# eurorack-passive-logic-or.net
KiCad netlist of a schematic drawn in EAGLE
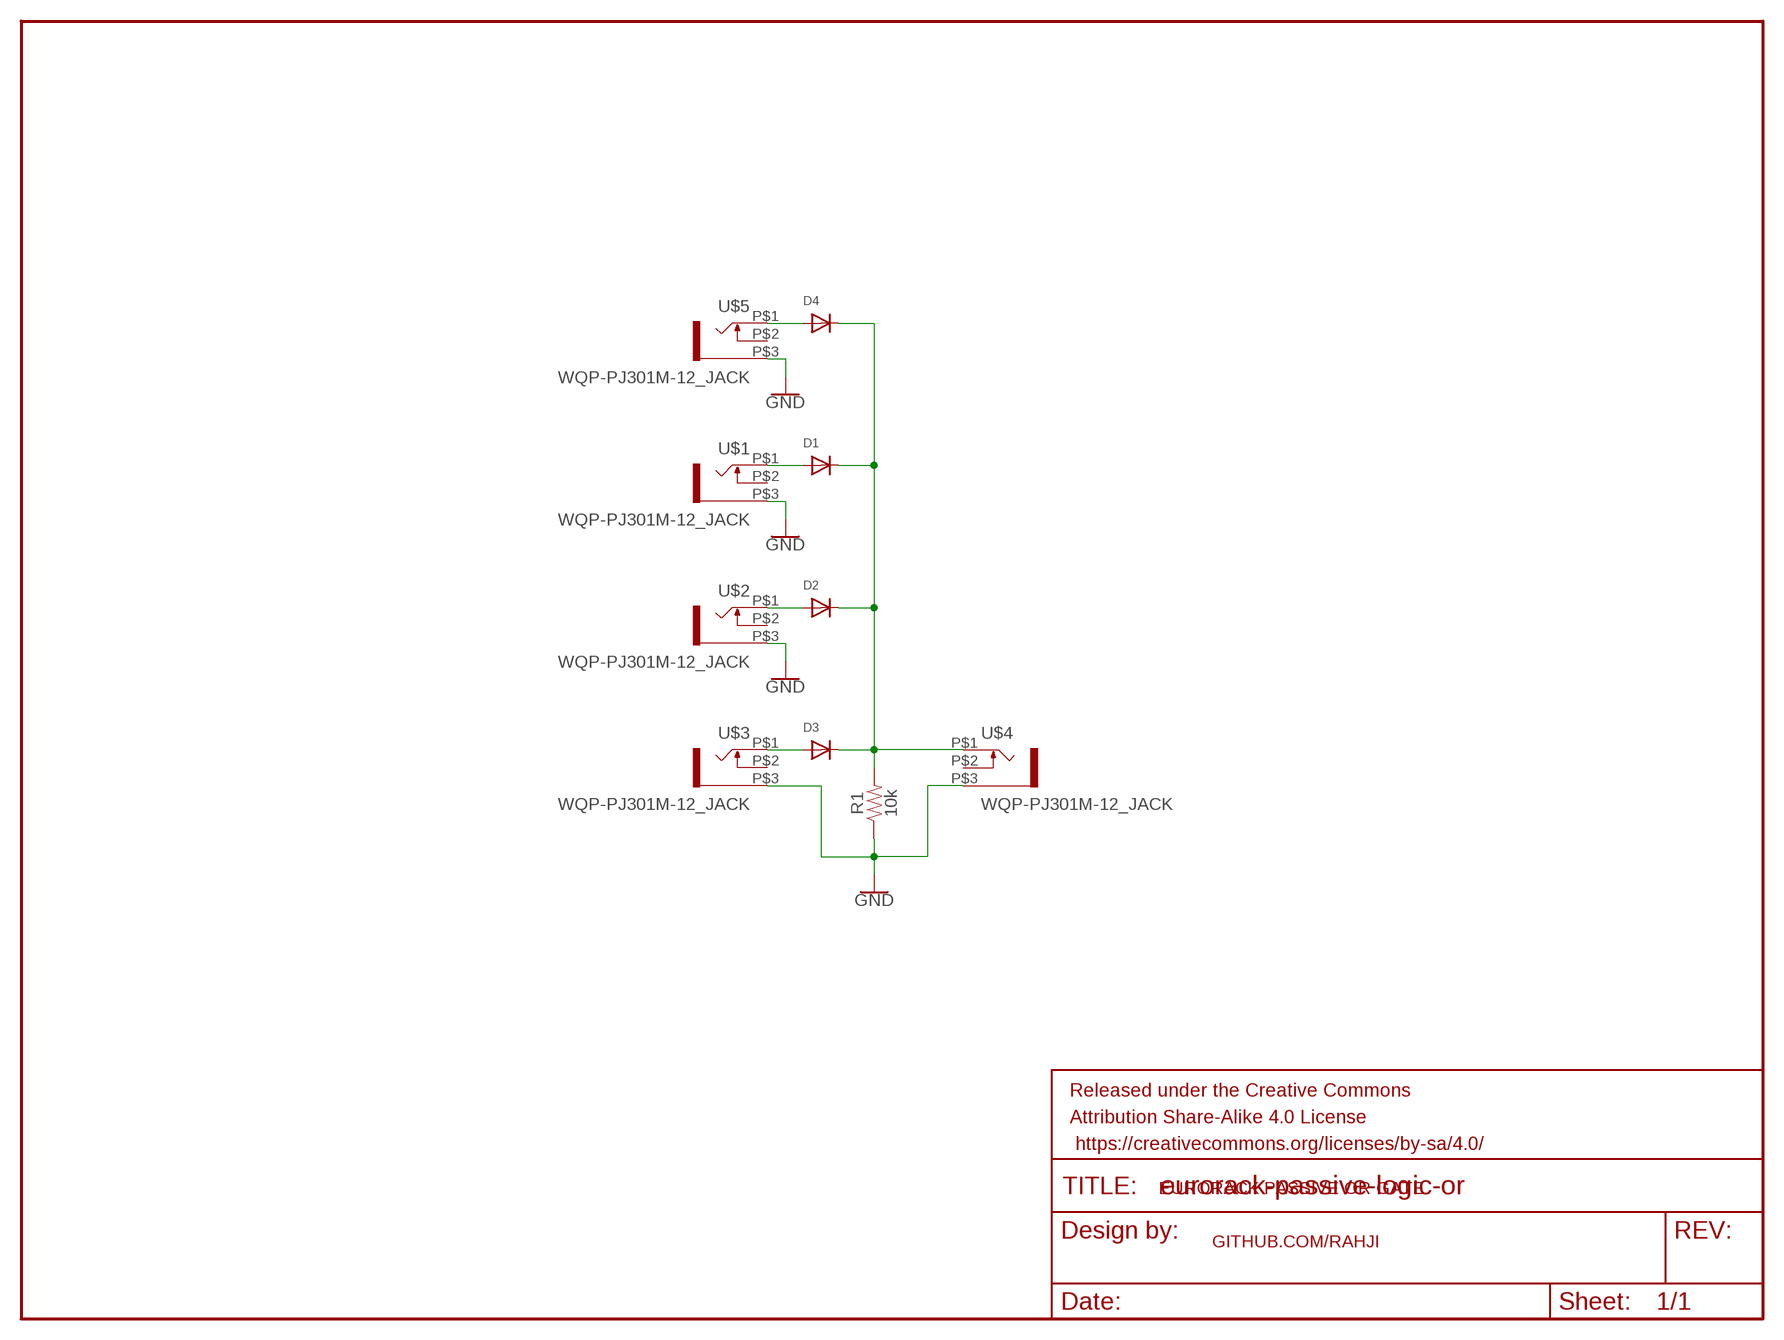
[diagram p0: schematic, sheet 1]

(export (version "E")
  (design (tool "Eeschema 10.0.6"))
  (components
    (comp (ref "D1")
      (value "DIODEDO-1N4148")
      (footprint "eagle-import:DO-1N4148")
      (libsource (lib "eagle-import") (part "DIODEDO-1N4148"))
    )
    (comp (ref "D2")
      (value "DIODEDO-1N4148")
      (footprint "eagle-import:DO-1N4148")
      (libsource (lib "eagle-import") (part "DIODEDO-1N4148"))
    )
    (comp (ref "D3")
      (value "DIODEDO-1N4148")
      (footprint "eagle-import:DO-1N4148")
      (libsource (lib "eagle-import") (part "DIODEDO-1N4148"))
    )
    (comp (ref "D4")
      (value "DIODEDO-1N4148")
      (footprint "eagle-import:DO-1N4148")
      (libsource (lib "eagle-import") (part "DIODEDO-1N4148"))
    )
    (comp (ref "FRAME1")
      (value "FRAME-LETTERNO_PACKAGE")
      (footprint "eagle-import:DUMMY")
      (fields (field (name "DESIGNER") "Nobody"))
      (libsource (lib "eagle-import") (part "FRAME-LETTERNO_PACKAGE"))
    )
    (comp (ref "R1")
      (value "10k")
      (footprint "eagle-import:AXIAL-0.3-KIT")
      (libsource (lib "eagle-import") (part "10KOHM-HORIZ_KIT-1/4W-5%"))
    )
    (comp (ref "U$1")
      (value "WQP-PJ301M-12_JACK")
      (footprint "eagle-import:WQP-PJ301M-12_JACK")
      (libsource (lib "eagle-import") (part "WQP-PJ301M-12_JACK"))
    )
    (comp (ref "U$2")
      (value "WQP-PJ301M-12_JACK")
      (footprint "eagle-import:WQP-PJ301M-12_JACK")
      (libsource (lib "eagle-import") (part "WQP-PJ301M-12_JACK"))
    )
    (comp (ref "U$3")
      (value "WQP-PJ301M-12_JACK")
      (footprint "eagle-import:WQP-PJ301M-12_JACK")
      (libsource (lib "eagle-import") (part "WQP-PJ301M-12_JACK"))
    )
    (comp (ref "U$4")
      (value "WQP-PJ301M-12_JACK")
      (footprint "eagle-import:WQP-PJ301M-12_JACK")
      (libsource (lib "eagle-import") (part "WQP-PJ301M-12_JACK"))
    )
    (comp (ref "U$5")
      (value "WQP-PJ301M-12_JACK")
      (footprint "eagle-import:WQP-PJ301M-12_JACK")
      (libsource (lib "eagle-import") (part "WQP-PJ301M-12_JACK"))
    )
  )
  (nets
    (net (code "1") (name "GND") (class "Default")
      (node (ref "R1") (pin "P$1") (pinfunction "1_P$1") (pintype "passive"))
      (node (ref "U$1") (pin "P$3") (pinfunction "1_P$3") (pintype "passive"))
      (node (ref "U$2") (pin "P$3") (pinfunction "1_P$3") (pintype "passive"))
      (node (ref "U$3") (pin "P$3") (pinfunction "1_P$3") (pintype "passive"))
      (node (ref "U$4") (pin "P$3") (pinfunction "1_P$3") (pintype "passive"))
      (node (ref "U$5") (pin "P$3") (pinfunction "1_P$3") (pintype "passive"))
    )
    (net (code "2") (name "Net-(R1-2)") (class "Default")
      (node (ref "D1") (pin "C") (pinfunction "C_C") (pintype "passive"))
      (node (ref "D2") (pin "C") (pinfunction "C_C") (pintype "passive"))
      (node (ref "D3") (pin "C") (pinfunction "C_C") (pintype "passive"))
      (node (ref "D4") (pin "C") (pinfunction "C_C") (pintype "passive"))
      (node (ref "R1") (pin "P$2") (pinfunction "2_P$2") (pintype "passive"))
      (node (ref "U$4") (pin "P$1") (pinfunction "2_P$1") (pintype "passive"))
    )
    (net (code "3") (name "Net-(U$1-2)") (class "Default")
      (node (ref "D1") (pin "A") (pinfunction "A_A") (pintype "passive"))
      (node (ref "U$1") (pin "P$1") (pinfunction "2_P$1") (pintype "passive"))
    )
    (net (code "4") (name "Net-(U$2-2)") (class "Default")
      (node (ref "D2") (pin "A") (pinfunction "A_A") (pintype "passive"))
      (node (ref "U$2") (pin "P$1") (pinfunction "2_P$1") (pintype "passive"))
    )
    (net (code "5") (name "Net-(U$3-2)") (class "Default")
      (node (ref "D3") (pin "A") (pinfunction "A_A") (pintype "passive"))
      (node (ref "U$3") (pin "P$1") (pinfunction "2_P$1") (pintype "passive"))
    )
    (net (code "6") (name "Net-(U$5-2)") (class "Default")
      (node (ref "D4") (pin "A") (pinfunction "A_A") (pintype "passive"))
      (node (ref "U$5") (pin "P$1") (pinfunction "2_P$1") (pintype "passive"))
    )
    (net (code "7") (name "unconnected-(U$1-3-PadP$2)") (class "Default")
      (node (ref "U$1") (pin "P$2") (pinfunction "3_P$2") (pintype "passive"))
    )
    (net (code "8") (name "unconnected-(U$2-3-PadP$2)") (class "Default")
      (node (ref "U$2") (pin "P$2") (pinfunction "3_P$2") (pintype "passive"))
    )
    (net (code "9") (name "unconnected-(U$3-3-PadP$2)") (class "Default")
      (node (ref "U$3") (pin "P$2") (pinfunction "3_P$2") (pintype "passive"))
    )
    (net (code "10") (name "unconnected-(U$4-3-PadP$2)") (class "Default")
      (node (ref "U$4") (pin "P$2") (pinfunction "3_P$2") (pintype "passive"))
    )
    (net (code "11") (name "unconnected-(U$5-3-PadP$2)") (class "Default")
      (node (ref "U$5") (pin "P$2") (pinfunction "3_P$2") (pintype "passive"))
    )
  )
)
